# SMPS.net
KiCad netlist of a schematic drawn in Altium Designer
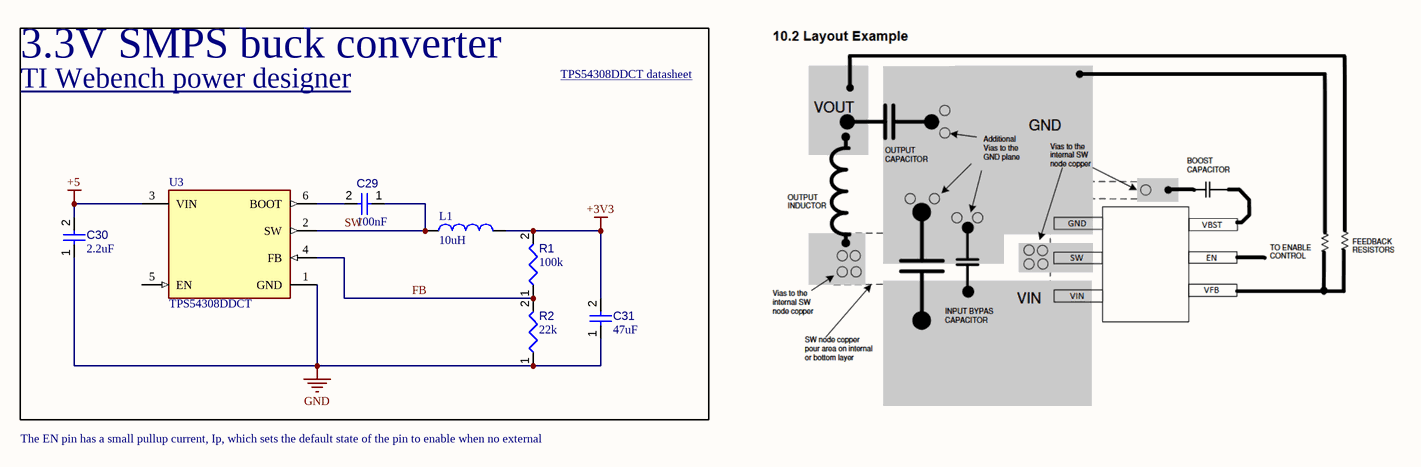
[diagram p0: SMPS.SchDoc]

(export (version "E")
  (design (tool "Eeschema 10.0.6"))
  (components
    (comp (ref "C29")
      (value "100nF")
      (footprint "CAPC0805(2012)145_L")
      (description "Chip Capacitor, 4.7µF +/-40%, 25V, 0805, Thickness 1.45 mm")
      (fields (field (name "TOLERANCE") "20%") (field (name "Comment") "Capacitor 4.7µF +/-40% 25V 0805"))
      (libsource (lib "ESD320") (part "CAP-NP-2"))
    )
    (comp (ref "C30")
      (value "2.2uF")
      (footprint "CAPC0603(1608)100_L")
      (description "Chip Capacitor, 4.7µF +/-20%, 10V, 0603, Thickness 1 mm")
      (fields (field (name "TOLERANCE") "10%") (field (name "Comment") "Capacitor 4.7µF +/-20% 10V 0603"))
      (libsource (lib "ESD320") (part "CAP-NP-2"))
    )
    (comp (ref "C31")
      (value "47uF")
      (footprint "CAPC1608X90X35ML15T15")
      (description "Chip Capacitor, 1 uF, +/- 10%, 16 V, 0603 (1608 Metric)")
      (fields (field (name "TOLERANCE") "10%") (field (name "Comment") "Capacitor 1uF +/- 10% 16V 0603"))
      (libsource (lib "ESD320") (part "CAP-NP-2"))
    )
    (comp (ref "L1")
      (value "10uH")
      (footprint "WE-PD2A_7850")
      (description "78477510 Inductor, Aec-Q200, 10Uh, Unshld, 2.3A Rohs Compliant: Yes")
      (fields (field (name "TOLERANCE") "20%"))
      (libsource (lib "Altium Content Vault") (part "Inductor - 1"))
    )
    (comp (ref "R1")
      (value "100k")
      (footprint "RESC0402(1005)_L")
      (description "121K 0.063W 1% 0402 (1005 Metric)  SMD")
      (fields (field (name "POWER") "63mW") (field (name "TOLERANCE") "1%"))
      (libsource (lib "ESD320") (part "121KR2F"))
    )
    (comp (ref "R2")
      (value "22k")
      (footprint "RESC0603(1608)_L")
      (description "120R 0.1W 5% 0603 (1608 Metric)  SMD")
      (fields (field (name "POWER") "100mW") (field (name "TOLERANCE") "5%"))
      (libsource (lib "ESD320") (part "120R3J"))
    )
    (comp (ref "U3")
      (value "TPS54308DDCT")
      (footprint "FP-DDC0006A-IPC_A")
      (description "IC REG BUCK ADJ 3A TSOT23-6")
      (libsource (lib "Altium Content Vault") (part "a1f5c2b37071bc968dc70eae1ee40ba"))
    )
  )
  (nets
    (net (code "1") (name "+3V3") (class "Default")
      (node (ref "C31") (pin "2") (pinfunction "2_2") (pintype "passive"))
      (node (ref "L1") (pin "2") (pinfunction "2_2") (pintype "passive"))
      (node (ref "R1") (pin "2") (pinfunction "2_2") (pintype "passive"))
    )
    (net (code "2") (name "+5") (class "Default")
      (node (ref "C30") (pin "2") (pinfunction "2_2") (pintype "passive"))
      (node (ref "U3") (pin "3") (pinfunction "VIN_3") (pintype "power_in"))
    )
    (net (code "3") (name "/FB") (class "Default")
      (node (ref "R1") (pin "1") (pinfunction "1_1") (pintype "passive"))
      (node (ref "R2") (pin "2") (pinfunction "2_2") (pintype "passive"))
      (node (ref "U3") (pin "4") (pinfunction "FB_4") (pintype "input"))
    )
    (net (code "4") (name "/SW") (class "Default")
      (node (ref "C29") (pin "1") (pinfunction "1_1") (pintype "passive"))
      (node (ref "L1") (pin "1") (pinfunction "1_1") (pintype "passive"))
      (node (ref "U3") (pin "2") (pinfunction "SW_2") (pintype "output"))
    )
    (net (code "5") (name "GND") (class "Default")
      (node (ref "C30") (pin "1") (pinfunction "1_1") (pintype "passive"))
      (node (ref "C31") (pin "1") (pinfunction "1_1") (pintype "passive"))
      (node (ref "R2") (pin "1") (pinfunction "1_1") (pintype "passive"))
      (node (ref "U3") (pin "1") (pinfunction "GND_1") (pintype "power_in"))
    )
    (net (code "6") (name "Net-(U3-BOOT)") (class "Default")
      (node (ref "C29") (pin "2") (pinfunction "2_2") (pintype "passive"))
      (node (ref "U3") (pin "6") (pinfunction "BOOT_6") (pintype "output"))
    )
    (net (code "7") (name "unconnected-(U3-EN-Pad5)") (class "Default")
      (node (ref "U3") (pin "5") (pinfunction "EN_5") (pintype "input"))
    )
  )
)
